# board_2_1.net
KiCad netlist of a schematic drawn in EAGLE
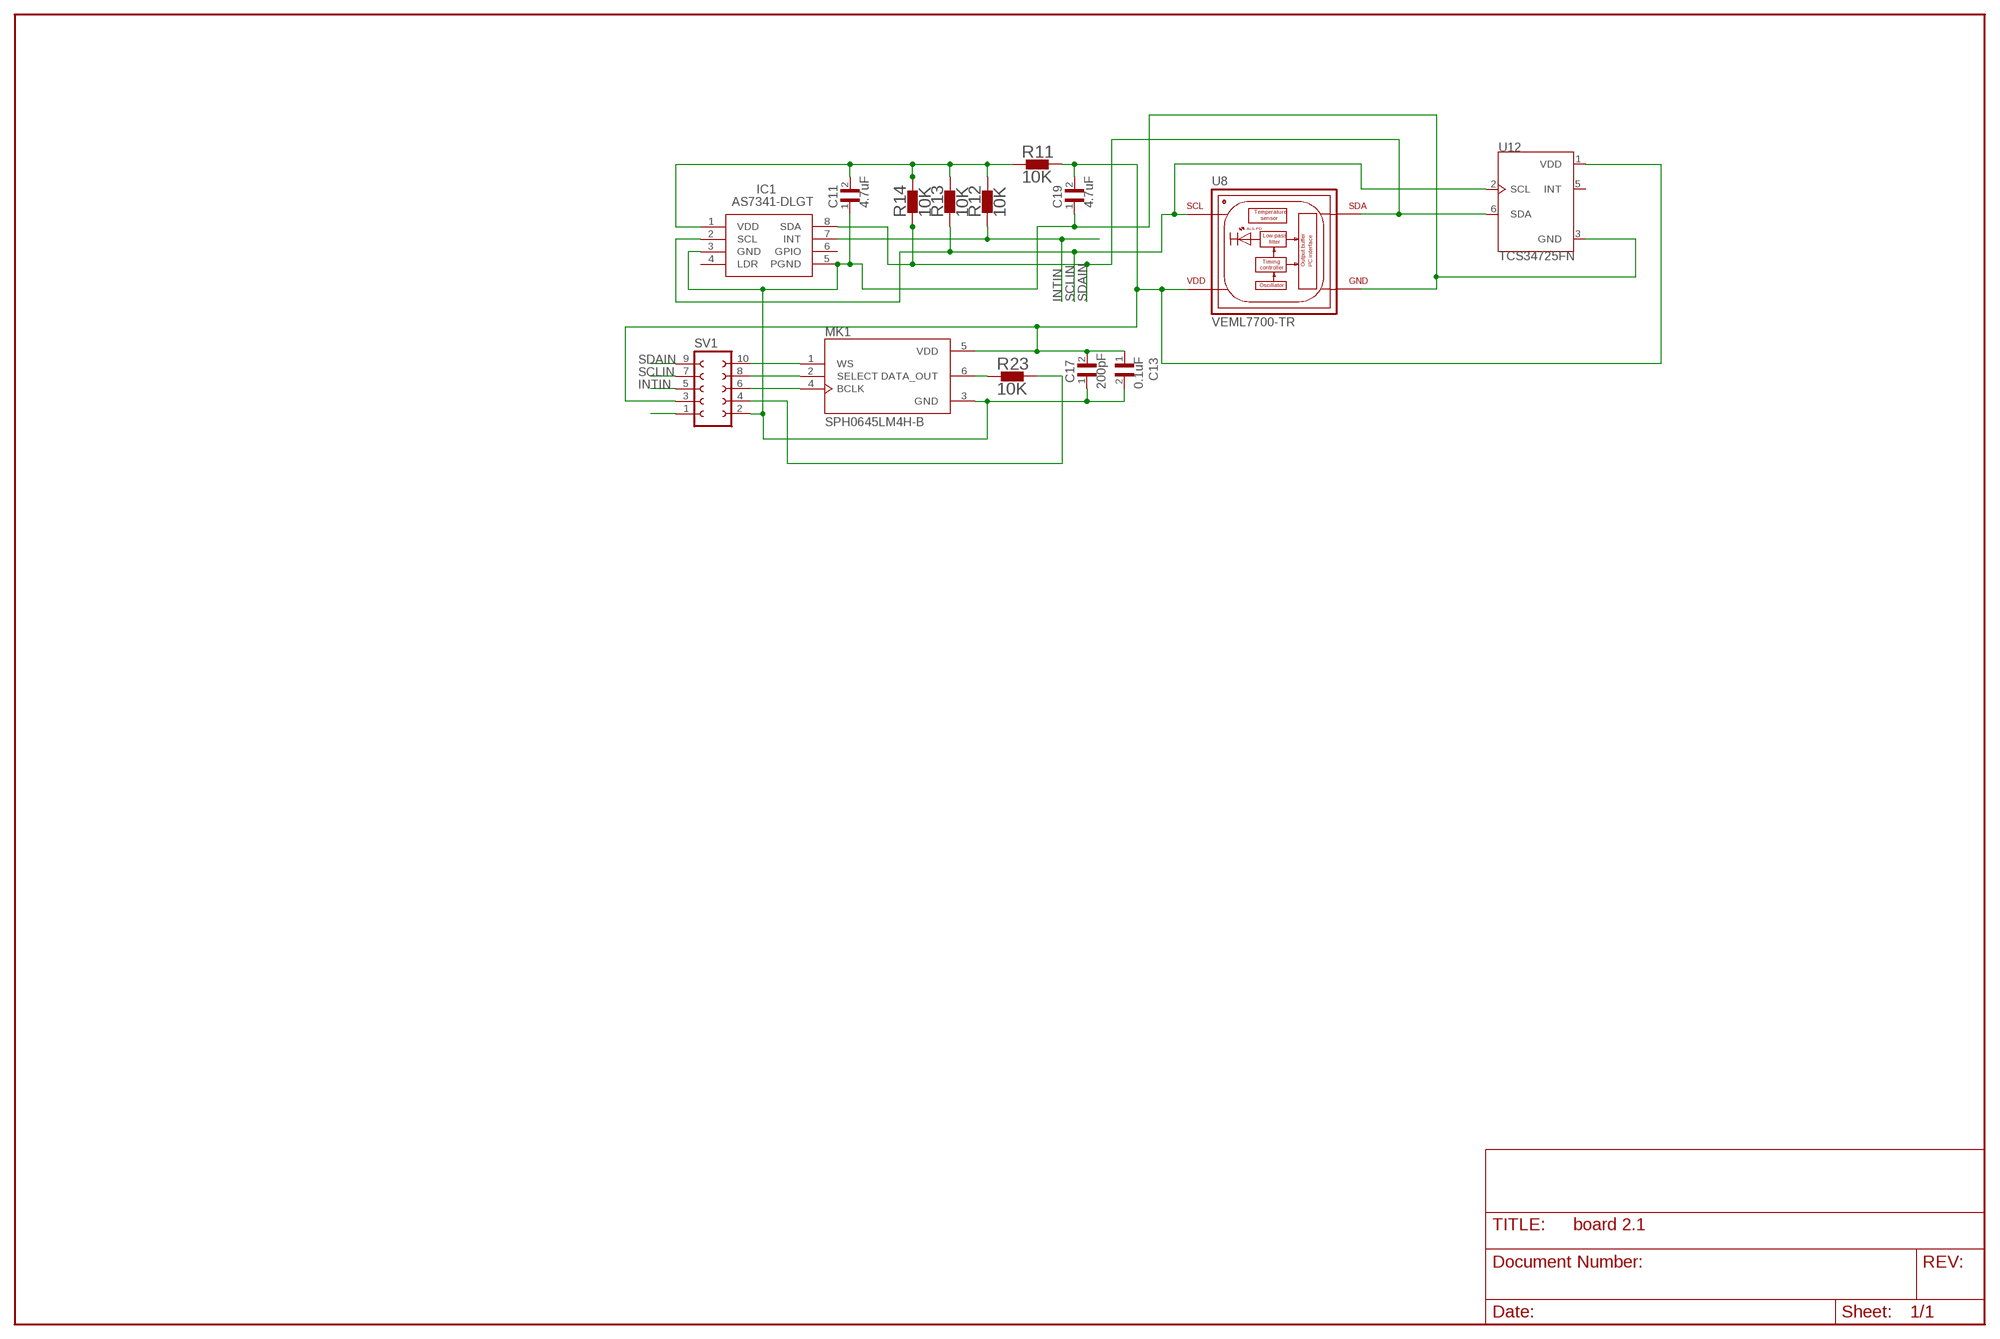
[diagram p0: schematic, sheet 1]

(export (version "E")
  (design (tool "Eeschema 10.0.6"))
  (components
    (comp (ref "C11")
      (value "4.7uF")
      (footprint "eagle-import:CAPC1608X90N")
      (fields
        (field (name "DIGI-KEY_PART_NUMBER") "1276-1045-1-ND")
        (field (name "MF") "Samsung Electro-Mechanics")
        (field (name "MP") "CL10A475KQ8NNNC")
      )
      (libsource (lib "eagle-import") (part "CL10A475KQ8NNNC"))
    )
    (comp (ref "C13")
      (value "0.1uF")
      (footprint "eagle-import:CAPC1005X55N")
      (fields
        (field (name "DIGI-KEY_PART_NUMBER") "1276-1043-1-ND")
        (field (name "MF") "Samsung Electro-Mechanics")
        (field (name "MP") "CL05A104KA5NNNC")
      )
      (libsource (lib "eagle-import") (part "CL05A104KA5NNNC"))
    )
    (comp (ref "C17")
      (value "200pF")
      (footprint "eagle-import:CAPC1608X90N")
      (fields
        (field (name "DIGI-KEY_PART_NUMBER") "1276-1018-1-ND")
        (field (name "MF") "Samsung")
        (field (name "MP") "CL10B102KB8NNNC")
      )
      (libsource (lib "eagle-import") (part "CL10B102KB8NNNC"))
    )
    (comp (ref "C19")
      (value "4.7uF")
      (footprint "eagle-import:CAPC1608X90N")
      (fields
        (field (name "DIGI-KEY_PART_NUMBER") "1276-1045-1-ND")
        (field (name "MF") "Samsung Electro-Mechanics")
        (field (name "MP") "CL10A475KQ8NNNC")
      )
      (libsource (lib "eagle-import") (part "CL10A475KQ8NNNC"))
    )
    (comp (ref "IC1")
      (value "AS7341-DLGT")
      (footprint "eagle-import:AS7341DLGT")
      (fields (field (name "MOUSER_PART_NUMBER") "985-AS7341-DLGT"))
      (libsource (lib "eagle-import") (part "AS7341-DLGT"))
    )
    (comp (ref "MK1")
      (value "SPH0645LM4H-B")
      (footprint "eagle-import:MIC_SPH0645LM4H-B")
      (fields (field (name "DIGI-KEY_PART_NUMBER") "423-1405-1-ND") (field (name "MF") "Knowles"))
      (libsource (lib "eagle-import") (part "SPH0645LM4H-B"))
    )
    (comp (ref "R11")
      (value "10K")
      (footprint "eagle-import:RESC2012X70N")
      (fields
        (field (name "DIGI-KEY_PART_NUMBER") "P16059CT-ND")
        (field (name "MF") "Panasonic")
        (field (name "MP") "ERJ-P06F1002V")
      )
      (libsource (lib "eagle-import") (part "ERJ-P06F1002V"))
    )
    (comp (ref "R12")
      (value "10K")
      (footprint "eagle-import:RESC2012X70N")
      (fields
        (field (name "DIGI-KEY_PART_NUMBER") "P16059CT-ND")
        (field (name "MF") "Panasonic")
        (field (name "MP") "ERJ-P06F1002V")
      )
      (libsource (lib "eagle-import") (part "ERJ-P06F1002V"))
    )
    (comp (ref "R13")
      (value "10K")
      (footprint "eagle-import:RESC2012X70N")
      (fields
        (field (name "DIGI-KEY_PART_NUMBER") "P16059CT-ND")
        (field (name "MF") "Panasonic")
        (field (name "MP") "ERJ-P06F1002V")
      )
      (libsource (lib "eagle-import") (part "ERJ-P06F1002V"))
    )
    (comp (ref "R14")
      (value "10K")
      (footprint "eagle-import:RESC2012X70N")
      (fields
        (field (name "DIGI-KEY_PART_NUMBER") "P16059CT-ND")
        (field (name "MF") "Panasonic")
        (field (name "MP") "ERJ-P06F1002V")
      )
      (libsource (lib "eagle-import") (part "ERJ-P06F1002V"))
    )
    (comp (ref "R23")
      (value "10K")
      (footprint "eagle-import:RESC2012X70N")
      (fields
        (field (name "DIGI-KEY_PART_NUMBER") "P16059CT-ND")
        (field (name "MF") "Panasonic")
        (field (name "MP") "ERJ-P06F1002V")
      )
      (libsource (lib "eagle-import") (part "ERJ-P06F1002V"))
    )
    (comp (ref "SV1")
      (value "FE05-2")
      (footprint "eagle-import:FE05-2")
      (libsource (lib "eagle-import") (part "FE05-2"))
    )
    (comp (ref "U8")
      (value "VEML7700-TR")
      (footprint "eagle-import:XDCR_VEML7700-TR")
      (fields (field (name "MF") "Vishay"))
      (libsource (lib "eagle-import") (part "VEML7700-TR"))
    )
    (comp (ref "U12")
      (value "TCS34725FN")
      (footprint "eagle-import:SON65P200X240X70-6N")
      (fields (field (name "MF") "ams"))
      (libsource (lib "eagle-import") (part "TCS34725FN"))
    )
  )
  (nets
    (net (code "1") (name "/INTIN") (class "Default")
      (node (ref "IC1") (pin "7") (pinfunction "INT_7") (pintype "bidirectional"))
      (node (ref "R12") (pin "1") (pinfunction "1_1") (pintype "passive"))
      (node (ref "SV1") (pin "5") (pinfunction "5_5") (pintype "passive"))
    )
    (net (code "2") (name "/SCLIN") (class "Default")
      (node (ref "IC1") (pin "2") (pinfunction "SCL_2") (pintype "bidirectional"))
      (node (ref "R13") (pin "1") (pinfunction "1_1") (pintype "passive"))
      (node (ref "SV1") (pin "7") (pinfunction "7_7") (pintype "passive"))
      (node (ref "U12") (pin "2") (pinfunction "SCL_2") (pintype "input"))
      (node (ref "U8") (pin "1") (pinfunction "SCL_1") (pintype "input"))
    )
    (net (code "3") (name "/SDAIN") (class "Default")
      (node (ref "IC1") (pin "8") (pinfunction "SDA_8") (pintype "bidirectional"))
      (node (ref "R14") (pin "1") (pinfunction "1_1") (pintype "passive"))
      (node (ref "SV1") (pin "9") (pinfunction "9_9") (pintype "passive"))
      (node (ref "U12") (pin "6") (pinfunction "SDA_6") (pintype "bidirectional"))
      (node (ref "U8") (pin "4") (pinfunction "SDA_4") (pintype "bidirectional"))
    )
    (net (code "4") (name "Net-(IC1-GND)") (class "Default")
      (node (ref "C11") (pin "1") (pinfunction "1_1") (pintype "passive"))
      (node (ref "C13") (pin "2") (pinfunction "2_2") (pintype "passive"))
      (node (ref "C17") (pin "1") (pinfunction "1_1") (pintype "passive"))
      (node (ref "C19") (pin "1") (pinfunction "1_1") (pintype "passive"))
      (node (ref "IC1") (pin "3") (pinfunction "GND_3") (pintype "bidirectional"))
      (node (ref "IC1") (pin "5") (pinfunction "PGND_5") (pintype "bidirectional"))
      (node (ref "MK1") (pin "3") (pinfunction "GND_3") (pintype "power_in"))
      (node (ref "SV1") (pin "2") (pinfunction "2_2") (pintype "passive"))
      (node (ref "U12") (pin "3") (pinfunction "GND_3") (pintype "power_in"))
      (node (ref "U8") (pin "3") (pinfunction "GND_3") (pintype "power_in"))
    )
    (net (code "5") (name "Net-(IC1-VDD)") (class "Default")
      (node (ref "C11") (pin "2") (pinfunction "2_2") (pintype "passive"))
      (node (ref "IC1") (pin "1") (pinfunction "VDD_1") (pintype "bidirectional"))
      (node (ref "R11") (pin "1") (pinfunction "1_1") (pintype "passive"))
      (node (ref "R12") (pin "2") (pinfunction "2_2") (pintype "passive"))
      (node (ref "R13") (pin "2") (pinfunction "2_2") (pintype "passive"))
      (node (ref "R14") (pin "2") (pinfunction "2_2") (pintype "passive"))
    )
    (net (code "6") (name "Net-(MK1-BCLK)") (class "Default")
      (node (ref "MK1") (pin "4") (pinfunction "BCLK_4") (pintype "input"))
      (node (ref "SV1") (pin "6") (pinfunction "6_6") (pintype "passive"))
    )
    (net (code "7") (name "Net-(MK1-DATA_OUT)") (class "Default")
      (node (ref "MK1") (pin "6") (pinfunction "DATA_OUT_6") (pintype "output"))
      (node (ref "R23") (pin "1") (pinfunction "1_1") (pintype "passive"))
    )
    (net (code "8") (name "Net-(MK1-SELECT)") (class "Default")
      (node (ref "MK1") (pin "2") (pinfunction "SELECT_2") (pintype "input"))
      (node (ref "SV1") (pin "8") (pinfunction "8_8") (pintype "passive"))
    )
    (net (code "9") (name "Net-(MK1-VDD)") (class "Default")
      (node (ref "C13") (pin "1") (pinfunction "1_1") (pintype "passive"))
      (node (ref "C17") (pin "2") (pinfunction "2_2") (pintype "passive"))
      (node (ref "C19") (pin "2") (pinfunction "2_2") (pintype "passive"))
      (node (ref "MK1") (pin "5") (pinfunction "VDD_5") (pintype "power_in"))
      (node (ref "R11") (pin "2") (pinfunction "2_2") (pintype "passive"))
      (node (ref "SV1") (pin "3") (pinfunction "3_3") (pintype "passive"))
      (node (ref "U12") (pin "1") (pinfunction "VDD_1") (pintype "power_in"))
      (node (ref "U8") (pin "2") (pinfunction "VDD_2") (pintype "power_in"))
    )
    (net (code "10") (name "Net-(MK1-WS)") (class "Default")
      (node (ref "MK1") (pin "1") (pinfunction "WS_1") (pintype "input"))
      (node (ref "SV1") (pin "10") (pinfunction "10_10") (pintype "passive"))
    )
    (net (code "11") (name "Net-(R23-Pad2)") (class "Default")
      (node (ref "R23") (pin "2") (pinfunction "2_2") (pintype "passive"))
      (node (ref "SV1") (pin "4") (pinfunction "4_4") (pintype "passive"))
    )
    (net (code "12") (name "unconnected-(IC1-GPIO-Pad6)") (class "Default")
      (node (ref "IC1") (pin "6") (pinfunction "GPIO_6") (pintype "bidirectional"))
    )
    (net (code "13") (name "unconnected-(IC1-LDR-Pad4)") (class "Default")
      (node (ref "IC1") (pin "4") (pinfunction "LDR_4") (pintype "bidirectional"))
    )
    (net (code "14") (name "unconnected-(SV1-Pad1)") (class "Default")
      (node (ref "SV1") (pin "1") (pinfunction "1_1") (pintype "passive"))
    )
    (net (code "15") (name "unconnected-(U12-INT-Pad5)") (class "Default")
      (node (ref "U12") (pin "5") (pinfunction "INT_5") (pintype "output"))
    )
  )
)
